# SH-C30L-V1_0.net
KiCad netlist of a schematic drawn in Altium Designer
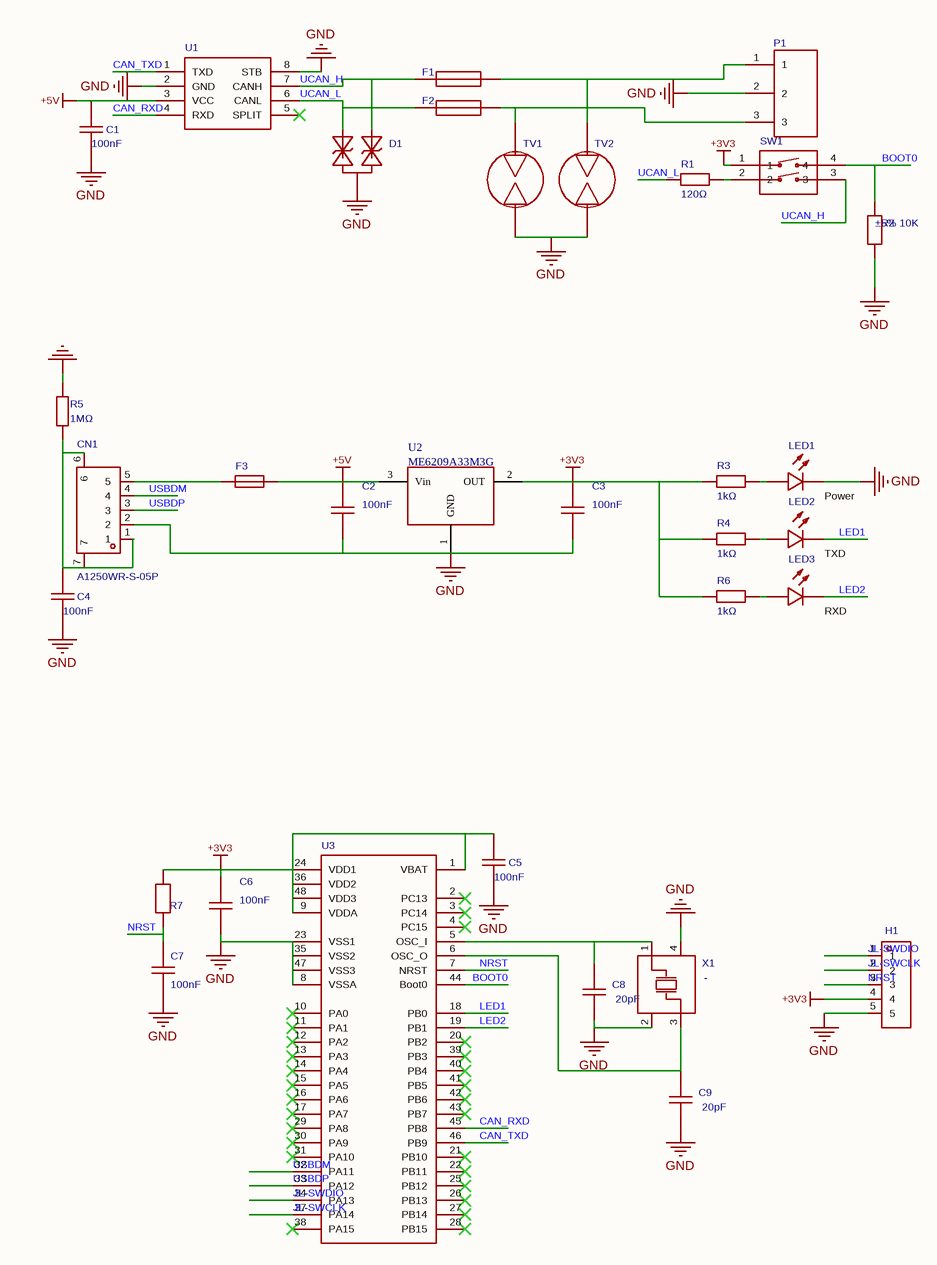
[diagram p0: SH-C30L-V1.0.SchDoc]

(export (version "E")
  (design (tool "Eeschema 10.0.6"))
  (components
    (comp (ref "C1")
      (value "100nF")
      (footprint "C0402")
      (description "Capacitance:100nF;Tolerance:±10%;Rated Voltage:50V;Temp. Coefficient:X7R;")
      (fields (field (name "MANUFACTURER") "IHHEC") (field (name "MANUFACTURERPART") "C0402X104K050T"))
      (libsource (lib "altium-import") (part "root_1_C0402X104K050T_"))
    )
    (comp (ref "C2")
      (value "100nF")
      (footprint "C0402")
      (description "Capacitance:100nF;Tolerance:±10%;Rated Voltage:50V;Temp. Coefficient:X7R;")
      (fields (field (name "MANUFACTURER") "IHHEC") (field (name "MANUFACTURERPART") "C0402X104K050T"))
      (libsource (lib "altium-import") (part "root_1_C0402X104K050T_"))
    )
    (comp (ref "C3")
      (value "100nF")
      (footprint "C0402")
      (description "Capacitance:100nF;Tolerance:±10%;Rated Voltage:50V;Temp. Coefficient:X7R;")
      (fields (field (name "MANUFACTURER") "IHHEC") (field (name "MANUFACTURERPART") "C0402X104K050T"))
      (libsource (lib "altium-import") (part "root_1_C0402X104K050T_"))
    )
    (comp (ref "C4")
      (value "100nF")
      (footprint "C0402")
      (description "Capacitance:100nF;Tolerance:±10%;Rated Voltage:50V;Temp. Coefficient:X7R;")
      (fields (field (name "MANUFACTURER") "IHHEC") (field (name "MANUFACTURERPART") "C0402X104K050T"))
      (libsource (lib "altium-import") (part "root_1_C0402X104K050T_"))
    )
    (comp (ref "C5")
      (value "100nF")
      (footprint "C0402")
      (description "Capacitance:100nF;Tolerance:±10%;Rated Voltage:50V;Temp. Coefficient:X7R;")
      (fields (field (name "MANUFACTURER") "IHHEC") (field (name "MANUFACTURERPART") "C0402X104K050T"))
      (libsource (lib "altium-import") (part "root_1_C0402X104K050T_"))
    )
    (comp (ref "C6")
      (value "100nF")
      (footprint "C0402")
      (description "Capacitance:100nF;Tolerance:±10%;Rated Voltage:50V;Temp. Coefficient:X7R;")
      (fields (field (name "MANUFACTURER") "IHHEC") (field (name "MANUFACTURERPART") "C0402X104K050T"))
      (libsource (lib "altium-import") (part "root_1_C0402X104K050T_"))
    )
    (comp (ref "C7")
      (value "100nF")
      (footprint "C0402")
      (description "Capacitance:100nF;Tolerance:±10%;Rated Voltage:50V;Temp. Coefficient:X7R;")
      (fields (field (name "MANUFACTURER") "IHHEC") (field (name "MANUFACTURERPART") "C0402X104K050T"))
      (libsource (lib "altium-import") (part "root_1_C0402X104K050T_"))
    )
    (comp (ref "C8")
      (value "20pF")
      (footprint "C0402")
      (description "Capacitance:20pF;Tolerance:±5%;Rated Voltage:50V;Temp. Coefficient:C0G;")
      (fields (field (name "MANUFACTURER") "muRata") (field (name "MANUFACTURERPART") "GRM1555C1H200JA01D"))
      (libsource (lib "altium-import") (part "root_3_GRM1555C1H200JA01D_"))
    )
    (comp (ref "C9")
      (value "20pF")
      (footprint "C0402")
      (description "Capacitance:20pF;Tolerance:±5%;Rated Voltage:50V;Temp. Coefficient:C0G;")
      (fields (field (name "MANUFACTURER") "muRata") (field (name "MANUFACTURERPART") "GRM1555C1H200JA01D"))
      (libsource (lib "altium-import") (part "root_1_GRM1555C1H200JA01D_"))
    )
    (comp (ref "CN1")
      (value "A1250WR-S-05P")
      (footprint "CONN-SMD_HF-P1.25-5P")
      (fields (field (name "MANUFACTURER") "HR"))
      (libsource (lib "altium-import") (part "root_2_A1250WR-S-05P_"))
    )
    (comp (ref "D1")
      (value "~")
      (footprint "SOT-23-3_L2.9-W1.3-P1.90-LS2.4-BR")
      (fields (field (name "MANUFACTURER") "TECH PUBLIC") (field (name "MANUFACTURERPART") "TPPESD12VL2BT"))
      (libsource (lib "altium-import") (part "root_2_TPPESD12VL2BT_"))
    )
    (comp (ref "F1")
      (value "~")
      (footprint "F1206")
      (fields (field (name "MANUFACTURER") "BHFUSE") (field (name "MANUFACTURERPART") "BSMD1206-020-24V"))
      (libsource (lib "altium-import") (part "root_0_BSMD1206-020-24V_"))
    )
    (comp (ref "F2")
      (value "~")
      (footprint "F1206")
      (fields (field (name "MANUFACTURER") "BHFUSE") (field (name "MANUFACTURERPART") "BSMD1206-020-24V"))
      (libsource (lib "altium-import") (part "root_0_BSMD1206-020-24V_"))
    )
    (comp (ref "F3")
      (value "~")
      (footprint "F0805")
      (description "Max Voltage:24V;Max Current:100A;Hold Current:100mA;Trip Current:300mA;")
      (fields (field (name "MANUFACTURER") "FUZETEC") (field (name "MANUFACTURERPART") "FSMD010-24-0805-R"))
      (libsource (lib "altium-import") (part "root_0_FSMD010-24-0805-R_"))
    )
    (comp (ref "H1")
      (value "~")
      (footprint "HDR-TH_5P-P2.54-V-M")
      (fields (field (name "MANUFACTURER") "XFCN") (field (name "MANUFACTURERPART") "PZ254V-11-05P"))
      (libsource (lib "altium-import") (part "root_0_PZ254V-11-05P_"))
    )
    (comp (ref "LED1")
      (value "~")
      (footprint "LED0603-RD_RED")
      (description "Emitted Color:Red;")
      (fields (field (name "MANUFACTURER") "NationStar") (field (name "MANUFACTURERPART") "NCD0603R1"))
      (libsource (lib "altium-import") (part "root_0_mirrored_NCD0603R1_C84263_"))
    )
    (comp (ref "LED2")
      (value "~")
      (footprint "LED0603-RD")
      (description "Emitted Color:Emerald Green;")
      (fields (field (name "MANUFACTURER") "NationStar") (field (name "MANUFACTURERPART") "NCD0603G1"))
      (libsource (lib "altium-import") (part "root_0_NCD0603G1_"))
    )
    (comp (ref "LED3")
      (value "~")
      (footprint "LED0603-RD")
      (description "Emitted Color:Emerald Green;")
      (fields (field (name "MANUFACTURER") "NationStar") (field (name "MANUFACTURERPART") "NCD0603G1"))
      (libsource (lib "altium-import") (part "root_0_NCD0603G1_"))
    )
    (comp (ref "P1")
      (value "~")
      (footprint "CONN-TH_3P-P3.81_WJ124-3.81-3P")
      (fields (field (name "MANUFACTURER") "KANGNEX") (field (name "MANUFACTURERPART") "WJ124-3.81-3P"))
      (libsource (lib "altium-import") (part "root_0_mirrored_WJ124-3.81-3P_"))
    )
    (comp (ref "R1")
      (value "120Ω")
      (footprint "R0805")
      (fields
        (field (name "MANUFACTURER") "UNI-ROYAL")
        (field (name "MANUFACTURERPART") "TC0525F1200T5E")
        (field (name "TOLERANCE") "±1%")
      )
      (libsource (lib "altium-import") (part "root_0_TC0525F1200T5E_"))
    )
    (comp (ref "R2")
      (value "~")
      (footprint "R0402")
      (fields
        (field (name "LCSC PART NAME") "±5% 10K")
        (field (name "MANUFACTURER") "VO")
        (field (name "MANUFACTURERPART") "SCR0402J10K")
      )
      (libsource (lib "altium-import") (part "root_1_SCR0402J10K_"))
    )
    (comp (ref "R3")
      (value "1kΩ")
      (footprint "R0402")
      (fields
        (field (name "MANUFACTURER") "YAGEO")
        (field (name "MANUFACTURERPART") "RC0402JR-071KL")
        (field (name "TOLERANCE") "±5%")
      )
      (libsource (lib "altium-import") (part "root_0_RC0402JR-071KL_"))
    )
    (comp (ref "R4")
      (value "1kΩ")
      (footprint "R0402")
      (fields
        (field (name "MANUFACTURER") "YAGEO")
        (field (name "MANUFACTURERPART") "RC0402JR-071KL")
        (field (name "TOLERANCE") "±5%")
      )
      (libsource (lib "altium-import") (part "root_0_RC0402JR-071KL_"))
    )
    (comp (ref "R5")
      (value "1MΩ")
      (footprint "R0603")
      (fields
        (field (name "MANUFACTURER") "UNI-ROYAL")
        (field (name "MANUFACTURERPART") "0603WAJ0105T5E")
        (field (name "TOLERANCE") "±5%")
      )
      (libsource (lib "altium-import") (part "root_3_0603WAJ0105T5E_"))
    )
    (comp (ref "R6")
      (value "1kΩ")
      (footprint "R0402")
      (fields
        (field (name "MANUFACTURER") "YAGEO")
        (field (name "MANUFACTURERPART") "RC0402JR-071KL")
        (field (name "TOLERANCE") "±5%")
      )
      (libsource (lib "altium-import") (part "root_0_RC0402JR-071KL_"))
    )
    (comp (ref "R7")
      (value "~")
      (footprint "R0402")
      (fields (field (name "MANUFACTURER") "VO") (field (name "MANUFACTURERPART") "SCR0402J10K"))
      (libsource (lib "altium-import") (part "root_1_SCR0402J10K_"))
    )
    (comp (ref "SW1")
      (value "~")
      (footprint "SW-SMD_4P-L6.5-W6.0-P2.54-LS9.8")
      (description "SMD DIP switch, 2.54mm pitch, 2 positions, side-actuated long lever")
      (fields (field (name "MANUFACTURERPART") "NPM-02-V-T/R"))
      (libsource (lib "altium-import") (part "root_0_NPM-02-V-T/R_"))
    )
    (comp (ref "TV1")
      (value "~")
      (footprint "DIO-DT-SMD_L4.5-W3.2")
      (fields
        (field (name "MANUFACTURER") "RUILON")
        (field (name "MANUFACTURERPART") "SMD4532-090NF")
        (field (name "TOLERANCE") "±30%")
      )
      (libsource (lib "altium-import") (part "root_0_SMD4532-090NF_"))
    )
    (comp (ref "TV2")
      (value "~")
      (footprint "DIO-DT-SMD_L4.5-W3.2")
      (fields
        (field (name "MANUFACTURER") "RUILON")
        (field (name "MANUFACTURERPART") "SMD4532-090NF")
        (field (name "TOLERANCE") "±30%")
      )
      (libsource (lib "altium-import") (part "root_0_SMD4532-090NF_"))
    )
    (comp (ref "U1")
      (value "~")
      (footprint "SOIC-8_L5.0-W4.0-P1.27-LS6.0-BL")
      (description "Type:Transceiver;Protocol:CAN Bus;")
      (fields (field (name "MANUFACTURER") "NXP") (field (name "MANUFACTURERPART") "TJA1040T/CM,118"))
      (libsource (lib "altium-import") (part "root_0_TJA1040T/CM,118_"))
    )
    (comp (ref "U2")
      (value "ME6209A33M3G")
      (footprint "SOT-23(SOT-23-3)")
      (libsource (lib "altium-import") (part "root_0_ME6209A33M3G_"))
    )
    (comp (ref "U3")
      (value "~")
      (footprint "LQFP-48_L7.0-W7.0-P0.50-LS9.0-BL")
      (description "CPU Core:ARM® Cortex®-M0;Supply Voltage:1.65V ~ 3.6V;")
      (fields (field (name "MANUFACTURER") "ST") (field (name "MANUFACTURERPART") "STM32F072C8T6"))
      (libsource (lib "altium-import") (part "root_0_STM32F072C8T6_"))
    )
    (comp (ref "X1")
      (value "-")
      (footprint "OSC-SMD_4P-L3.2-W2.5-BL")
      (fields (field (name "MANUFACTURER") "TKD") (field (name "MANUFACTURERPART") "SX32Y024000BC1T"))
      (libsource (lib "altium-import") (part "root_3_SX32Y024000BC1T_"))
    )
  )
  (nets
    (net (code "1") (name "+3V3") (class "Default")
      (node (ref "C3") (pin "2") (pinfunction "2_2") (pintype "passive"))
      (node (ref "C5") (pin "2") (pinfunction "2_2") (pintype "passive"))
      (node (ref "C6") (pin "2") (pinfunction "2_2") (pintype "passive"))
      (node (ref "H1") (pin "4") (pinfunction "4_4") (pintype "passive"))
      (node (ref "R3") (pin "1") (pinfunction "1_1") (pintype "passive"))
      (node (ref "R4") (pin "1") (pinfunction "1_1") (pintype "passive"))
      (node (ref "R6") (pin "1") (pinfunction "1_1") (pintype "passive"))
      (node (ref "R7") (pin "2") (pinfunction "2_2") (pintype "passive"))
      (node (ref "SW1") (pin "1") (pinfunction "1_1") (pintype "passive"))
      (node (ref "U2") (pin "2") (pinfunction "OUT_2") (pintype "passive"))
      (node (ref "U3") (pin "1") (pinfunction "VBAT_1") (pintype "passive"))
      (node (ref "U3") (pin "24") (pinfunction "VDD1_24") (pintype "passive"))
      (node (ref "U3") (pin "36") (pinfunction "VDD2_36") (pintype "passive"))
      (node (ref "U3") (pin "48") (pinfunction "VDD3_48") (pintype "passive"))
      (node (ref "U3") (pin "9") (pinfunction "VDDA_9") (pintype "passive"))
    )
    (net (code "2") (name "+5V") (class "Default")
      (node (ref "C1") (pin "2") (pinfunction "2_2") (pintype "passive"))
      (node (ref "C2") (pin "2") (pinfunction "2_2") (pintype "passive"))
      (node (ref "F3") (pin "2") (pinfunction "2_2") (pintype "passive"))
      (node (ref "U1") (pin "3") (pinfunction "VCC_3") (pintype "passive"))
      (node (ref "U2") (pin "3") (pinfunction "Vin_3") (pintype "passive"))
    )
    (net (code "3") (name "/BOOT0") (class "Default")
      (node (ref "R2") (pin "2") (pinfunction "2_2") (pintype "passive"))
      (node (ref "SW1") (pin "4") (pinfunction "4_4") (pintype "passive"))
      (node (ref "U3") (pin "44") (pinfunction "Boot0_44") (pintype "passive"))
    )
    (net (code "4") (name "/CAN_RXD") (class "Default")
      (node (ref "U1") (pin "4") (pinfunction "RXD_4") (pintype "passive"))
      (node (ref "U3") (pin "45") (pinfunction "PB8_45") (pintype "passive"))
    )
    (net (code "5") (name "/CAN_TXD") (class "Default")
      (node (ref "U1") (pin "1") (pinfunction "TXD_1") (pintype "passive"))
      (node (ref "U3") (pin "46") (pinfunction "PB9_46") (pintype "passive"))
    )
    (net (code "6") (name "/JL-SWCLK") (class "Default")
      (node (ref "H1") (pin "2") (pinfunction "2_2") (pintype "passive"))
      (node (ref "U3") (pin "37") (pinfunction "PA14_37") (pintype "passive"))
    )
    (net (code "7") (name "/JL-SWDIO") (class "Default")
      (node (ref "H1") (pin "1") (pinfunction "1_1") (pintype "passive"))
      (node (ref "U3") (pin "34") (pinfunction "PA13_34") (pintype "passive"))
    )
    (net (code "8") (name "/LED1") (class "Default")
      (node (ref "LED2") (pin "1") (pinfunction "K_1") (pintype "passive"))
      (node (ref "U3") (pin "18") (pinfunction "PB0_18") (pintype "passive"))
    )
    (net (code "9") (name "/LED2") (class "Default")
      (node (ref "LED3") (pin "1") (pinfunction "K_1") (pintype "passive"))
      (node (ref "U3") (pin "19") (pinfunction "PB1_19") (pintype "passive"))
    )
    (net (code "10") (name "/NRST") (class "Default")
      (node (ref "C7") (pin "2") (pinfunction "2_2") (pintype "passive"))
      (node (ref "H1") (pin "3") (pinfunction "3_3") (pintype "passive"))
      (node (ref "R7") (pin "1") (pinfunction "1_1") (pintype "passive"))
      (node (ref "U3") (pin "7") (pinfunction "NRST_7") (pintype "passive"))
    )
    (net (code "11") (name "/UCAN_H") (class "Default")
      (node (ref "D1") (pin "1") (pinfunction "1_1") (pintype "passive"))
      (node (ref "F1") (pin "1") (pinfunction "1_1") (pintype "passive"))
      (node (ref "SW1") (pin "3") (pinfunction "3_3") (pintype "passive"))
      (node (ref "U1") (pin "7") (pinfunction "CANH_7") (pintype "passive"))
    )
    (net (code "12") (name "/UCAN_L") (class "Default")
      (node (ref "D1") (pin "2") (pinfunction "2_2") (pintype "passive"))
      (node (ref "F2") (pin "1") (pinfunction "1_1") (pintype "passive"))
      (node (ref "R1") (pin "1") (pinfunction "1_1") (pintype "passive"))
      (node (ref "U1") (pin "6") (pinfunction "CANL_6") (pintype "passive"))
    )
    (net (code "13") (name "/USBDM") (class "Default")
      (node (ref "CN1") (pin "4") (pinfunction "4_4") (pintype "passive"))
      (node (ref "U3") (pin "32") (pinfunction "PA11_32") (pintype "passive"))
    )
    (net (code "14") (name "/USBDP") (class "Default")
      (node (ref "CN1") (pin "3") (pinfunction "3_3") (pintype "passive"))
      (node (ref "U3") (pin "33") (pinfunction "PA12_33") (pintype "passive"))
    )
    (net (code "15") (name "GND") (class "Default")
      (node (ref "C1") (pin "1") (pinfunction "1_1") (pintype "passive"))
      (node (ref "C2") (pin "1") (pinfunction "1_1") (pintype "passive"))
      (node (ref "C3") (pin "1") (pinfunction "1_1") (pintype "passive"))
      (node (ref "C4") (pin "1") (pinfunction "1_1") (pintype "passive"))
      (node (ref "C5") (pin "1") (pinfunction "1_1") (pintype "passive"))
      (node (ref "C6") (pin "1") (pinfunction "1_1") (pintype "passive"))
      (node (ref "C7") (pin "1") (pinfunction "1_1") (pintype "passive"))
      (node (ref "C8") (pin "2") (pinfunction "2_2") (pintype "passive"))
      (node (ref "C9") (pin "1") (pinfunction "1_1") (pintype "passive"))
      (node (ref "CN1") (pin "2") (pinfunction "2_2") (pintype "passive"))
      (node (ref "D1") (pin "3") (pinfunction "3_3") (pintype "passive"))
      (node (ref "H1") (pin "5") (pinfunction "5_5") (pintype "passive"))
      (node (ref "LED1") (pin "1") (pinfunction "K_1") (pintype "passive"))
      (node (ref "P1") (pin "2") (pinfunction "2_2") (pintype "passive"))
      (node (ref "R2") (pin "1") (pinfunction "1_1") (pintype "passive"))
      (node (ref "R5") (pin "1") (pinfunction "1_1") (pintype "passive"))
      (node (ref "TV1") (pin "2") (pinfunction "2_2") (pintype "passive"))
      (node (ref "TV2") (pin "2") (pinfunction "2_2") (pintype "passive"))
      (node (ref "U1") (pin "2") (pinfunction "GND_2") (pintype "passive"))
      (node (ref "U1") (pin "8") (pinfunction "STB_8") (pintype "passive"))
      (node (ref "U2") (pin "1") (pinfunction "GND_1") (pintype "passive"))
      (node (ref "U3") (pin "23") (pinfunction "VSS1_23") (pintype "passive"))
      (node (ref "U3") (pin "35") (pinfunction "VSS2_35") (pintype "passive"))
      (node (ref "U3") (pin "47") (pinfunction "VSS3_47") (pintype "passive"))
      (node (ref "U3") (pin "8") (pinfunction "VSSA_8") (pintype "passive"))
      (node (ref "X1") (pin "2") (pinfunction "GND_2") (pintype "passive"))
      (node (ref "X1") (pin "4") (pinfunction "GND_4") (pintype "passive"))
    )
    (net (code "16") (name "Net-(C4-Pad2)") (class "Default")
      (node (ref "C4") (pin "2") (pinfunction "2_2") (pintype "passive"))
      (node (ref "CN1") (pin "1") (pinfunction "1_1") (pintype "passive"))
      (node (ref "CN1") (pin "6") (pinfunction "6_6") (pintype "passive"))
      (node (ref "CN1") (pin "7") (pinfunction "7_7") (pintype "passive"))
      (node (ref "R5") (pin "2") (pinfunction "2_2") (pintype "passive"))
    )
    (net (code "17") (name "Net-(CN1-Pad5)") (class "Default")
      (node (ref "CN1") (pin "5") (pinfunction "5_5") (pintype "passive"))
      (node (ref "F3") (pin "1") (pinfunction "1_1") (pintype "passive"))
    )
    (net (code "18") (name "Net-(F1-Pad2)") (class "Default")
      (node (ref "F1") (pin "2") (pinfunction "2_2") (pintype "passive"))
      (node (ref "P1") (pin "1") (pinfunction "1_1") (pintype "passive"))
      (node (ref "TV2") (pin "1") (pinfunction "1_1") (pintype "passive"))
    )
    (net (code "19") (name "Net-(F2-Pad2)") (class "Default")
      (node (ref "F2") (pin "2") (pinfunction "2_2") (pintype "passive"))
      (node (ref "P1") (pin "3") (pinfunction "3_3") (pintype "passive"))
      (node (ref "TV1") (pin "1") (pinfunction "1_1") (pintype "passive"))
    )
    (net (code "20") (name "Net-(LED1-A)") (class "Default")
      (node (ref "LED1") (pin "2") (pinfunction "A_2") (pintype "passive"))
      (node (ref "R3") (pin "2") (pinfunction "2_2") (pintype "passive"))
    )
    (net (code "21") (name "Net-(LED2-A)") (class "Default")
      (node (ref "LED2") (pin "2") (pinfunction "A_2") (pintype "passive"))
      (node (ref "R4") (pin "2") (pinfunction "2_2") (pintype "passive"))
    )
    (net (code "22") (name "Net-(LED3-A)") (class "Default")
      (node (ref "LED3") (pin "2") (pinfunction "A_2") (pintype "passive"))
      (node (ref "R6") (pin "2") (pinfunction "2_2") (pintype "passive"))
    )
    (net (code "23") (name "Net-(R1-Pad2)") (class "Default")
      (node (ref "R1") (pin "2") (pinfunction "2_2") (pintype "passive"))
      (node (ref "SW1") (pin "2") (pinfunction "2_2") (pintype "passive"))
    )
    (net (code "24") (name "Net-(U3-OSC_I)") (class "Default")
      (node (ref "C8") (pin "1") (pinfunction "1_1") (pintype "passive"))
      (node (ref "U3") (pin "5") (pinfunction "OSC_I_5") (pintype "passive"))
      (node (ref "X1") (pin "1") (pinfunction "OSC1_1") (pintype "passive"))
    )
    (net (code "25") (name "Net-(U3-OSC_O)") (class "Default")
      (node (ref "C9") (pin "2") (pinfunction "2_2") (pintype "passive"))
      (node (ref "U3") (pin "6") (pinfunction "OSC_O_6") (pintype "passive"))
      (node (ref "X1") (pin "3") (pinfunction "OSC2_3") (pintype "passive"))
    )
    (net (code "26") (name "unconnected-(U1-SPLIT-Pad5)") (class "Default")
      (node (ref "U1") (pin "5") (pinfunction "SPLIT_5") (pintype "passive+no_connect"))
    )
    (net (code "27") (name "unconnected-(U3-PA0-Pad10)") (class "Default")
      (node (ref "U3") (pin "10") (pinfunction "PA0_10") (pintype "passive+no_connect"))
    )
    (net (code "28") (name "unconnected-(U3-PA1-Pad11)") (class "Default")
      (node (ref "U3") (pin "11") (pinfunction "PA1_11") (pintype "passive+no_connect"))
    )
    (net (code "29") (name "unconnected-(U3-PA2-Pad12)") (class "Default")
      (node (ref "U3") (pin "12") (pinfunction "PA2_12") (pintype "passive+no_connect"))
    )
    (net (code "30") (name "unconnected-(U3-PA3-Pad13)") (class "Default")
      (node (ref "U3") (pin "13") (pinfunction "PA3_13") (pintype "passive+no_connect"))
    )
    (net (code "31") (name "unconnected-(U3-PA4-Pad14)") (class "Default")
      (node (ref "U3") (pin "14") (pinfunction "PA4_14") (pintype "passive+no_connect"))
    )
    (net (code "32") (name "unconnected-(U3-PA5-Pad15)") (class "Default")
      (node (ref "U3") (pin "15") (pinfunction "PA5_15") (pintype "passive+no_connect"))
    )
    (net (code "33") (name "unconnected-(U3-PA6-Pad16)") (class "Default")
      (node (ref "U3") (pin "16") (pinfunction "PA6_16") (pintype "passive+no_connect"))
    )
    (net (code "34") (name "unconnected-(U3-PA7-Pad17)") (class "Default")
      (node (ref "U3") (pin "17") (pinfunction "PA7_17") (pintype "passive+no_connect"))
    )
    (net (code "35") (name "unconnected-(U3-PA8-Pad29)") (class "Default")
      (node (ref "U3") (pin "29") (pinfunction "PA8_29") (pintype "passive+no_connect"))
    )
    (net (code "36") (name "unconnected-(U3-PA9-Pad30)") (class "Default")
      (node (ref "U3") (pin "30") (pinfunction "PA9_30") (pintype "passive+no_connect"))
    )
    (net (code "37") (name "unconnected-(U3-PA10-Pad31)") (class "Default")
      (node (ref "U3") (pin "31") (pinfunction "PA10_31") (pintype "passive+no_connect"))
    )
    (net (code "38") (name "unconnected-(U3-PA15-Pad38)") (class "Default")
      (node (ref "U3") (pin "38") (pinfunction "PA15_38") (pintype "passive+no_connect"))
    )
    (net (code "39") (name "unconnected-(U3-PB2-Pad20)") (class "Default")
      (node (ref "U3") (pin "20") (pinfunction "PB2_20") (pintype "passive+no_connect"))
    )
    (net (code "40") (name "unconnected-(U3-PB3-Pad39)") (class "Default")
      (node (ref "U3") (pin "39") (pinfunction "PB3_39") (pintype "passive+no_connect"))
    )
    (net (code "41") (name "unconnected-(U3-PB4-Pad40)") (class "Default")
      (node (ref "U3") (pin "40") (pinfunction "PB4_40") (pintype "passive+no_connect"))
    )
    (net (code "42") (name "unconnected-(U3-PB5-Pad41)") (class "Default")
      (node (ref "U3") (pin "41") (pinfunction "PB5_41") (pintype "passive+no_connect"))
    )
    (net (code "43") (name "unconnected-(U3-PB6-Pad42)") (class "Default")
      (node (ref "U3") (pin "42") (pinfunction "PB6_42") (pintype "passive+no_connect"))
    )
    (net (code "44") (name "unconnected-(U3-PB7-Pad43)") (class "Default")
      (node (ref "U3") (pin "43") (pinfunction "PB7_43") (pintype "passive+no_connect"))
    )
    (net (code "45") (name "unconnected-(U3-PB10-Pad21)") (class "Default")
      (node (ref "U3") (pin "21") (pinfunction "PB10_21") (pintype "passive+no_connect"))
    )
    (net (code "46") (name "unconnected-(U3-PB11-Pad22)") (class "Default")
      (node (ref "U3") (pin "22") (pinfunction "PB11_22") (pintype "passive+no_connect"))
    )
    (net (code "47") (name "unconnected-(U3-PB12-Pad25)") (class "Default")
      (node (ref "U3") (pin "25") (pinfunction "PB12_25") (pintype "passive+no_connect"))
    )
    (net (code "48") (name "unconnected-(U3-PB13-Pad26)") (class "Default")
      (node (ref "U3") (pin "26") (pinfunction "PB13_26") (pintype "passive+no_connect"))
    )
    (net (code "49") (name "unconnected-(U3-PB14-Pad27)") (class "Default")
      (node (ref "U3") (pin "27") (pinfunction "PB14_27") (pintype "passive+no_connect"))
    )
    (net (code "50") (name "unconnected-(U3-PB15-Pad28)") (class "Default")
      (node (ref "U3") (pin "28") (pinfunction "PB15_28") (pintype "passive+no_connect"))
    )
    (net (code "51") (name "unconnected-(U3-PC13-Pad2)") (class "Default")
      (node (ref "U3") (pin "2") (pinfunction "PC13_2") (pintype "passive+no_connect"))
    )
    (net (code "52") (name "unconnected-(U3-PC14-Pad3)") (class "Default")
      (node (ref "U3") (pin "3") (pinfunction "PC14_3") (pintype "passive+no_connect"))
    )
    (net (code "53") (name "unconnected-(U3-PC15-Pad4)") (class "Default")
      (node (ref "U3") (pin "4") (pinfunction "PC15_4") (pintype "passive+no_connect"))
    )
  )
)
